# usb_ppm-v0_2.net
KiCad netlist of a schematic drawn in EAGLE
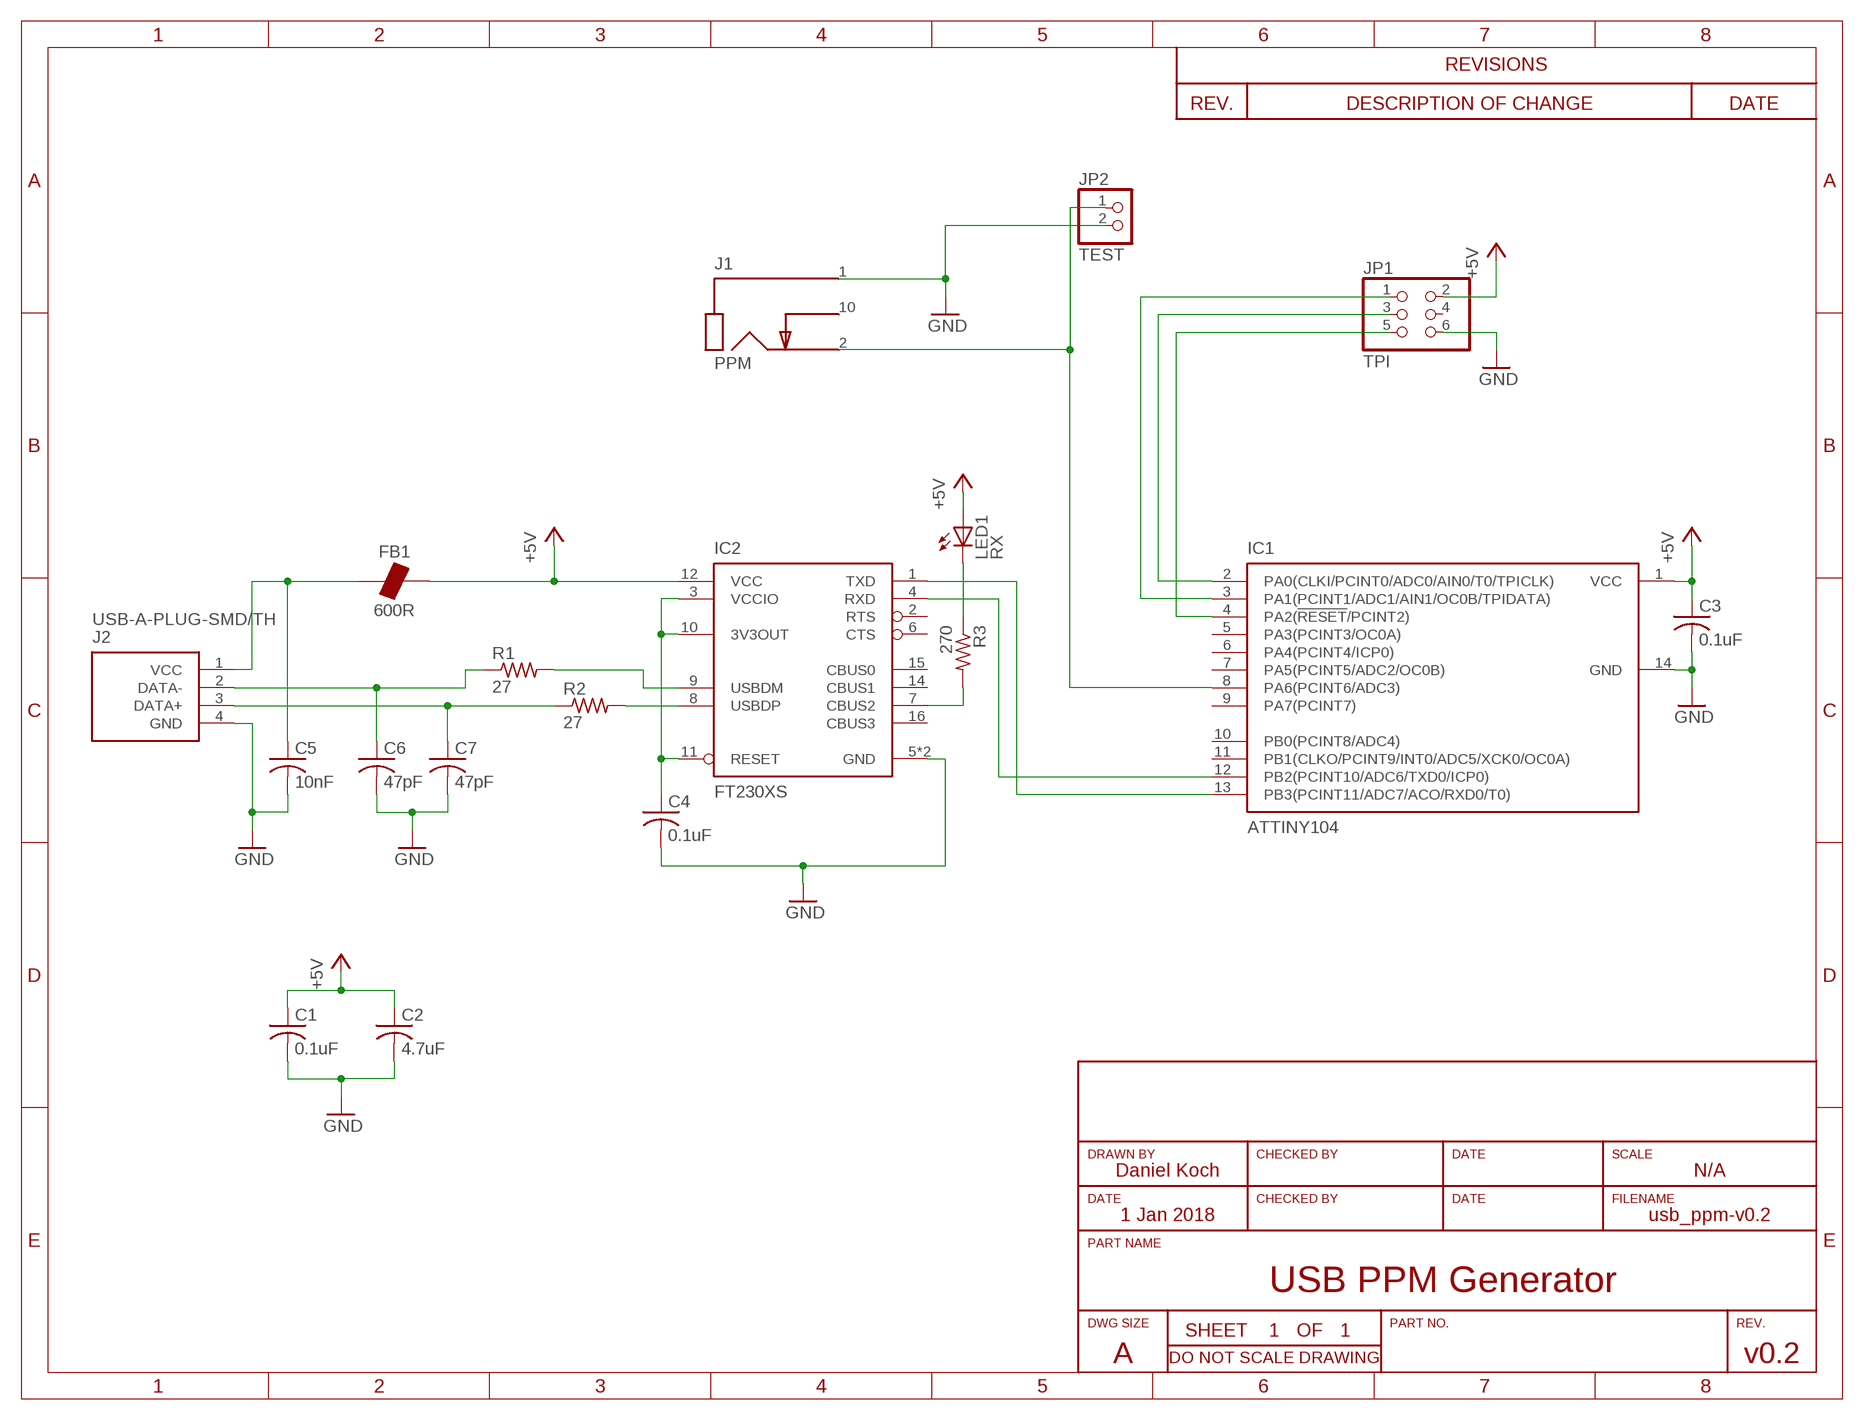
[diagram p0: schematic, sheet 1]

(export (version "E")
  (design (tool "Eeschema 10.0.6"))
  (components
    (comp (ref "C1")
      (value "0.1uF")
      (footprint "eagle-import:C0603")
      (libsource (lib "eagle-import") (part "C-USC0603"))
    )
    (comp (ref "C2")
      (value "4.7uF")
      (footprint "eagle-import:C0603")
      (libsource (lib "eagle-import") (part "C-USC0603"))
    )
    (comp (ref "C3")
      (value "0.1uF")
      (footprint "eagle-import:C0603")
      (libsource (lib "eagle-import") (part "C-USC0603"))
    )
    (comp (ref "C4")
      (value "0.1uF")
      (footprint "eagle-import:C0603")
      (libsource (lib "eagle-import") (part "C-USC0603"))
    )
    (comp (ref "C5")
      (value "10nF")
      (footprint "eagle-import:C0603")
      (libsource (lib "eagle-import") (part "C-USC0603"))
    )
    (comp (ref "C6")
      (value "47pF")
      (footprint "eagle-import:C0603")
      (libsource (lib "eagle-import") (part "C-USC0603"))
    )
    (comp (ref "C7")
      (value "47pF")
      (footprint "eagle-import:C0603")
      (libsource (lib "eagle-import") (part "C-USC0603"))
    )
    (comp (ref "FB1")
      (value "600R")
      (footprint "eagle-import:0603")
      (libsource (lib "eagle-import") (part "FB0603"))
    )
    (comp (ref "IC1")
      (value "ATTINY104")
      (footprint "eagle-import:SOIC-14")
      (libsource (lib "eagle-import") (part "ATTINY104"))
    )
    (comp (ref "IC2")
      (value "FT230XS")
      (footprint "eagle-import:SSOP-16")
      (libsource (lib "eagle-import") (part "FT230XS"))
    )
    (comp (ref "J1")
      (value "PPM")
      (footprint "eagle-import:MJ-3523-SMT")
      (libsource (lib "eagle-import") (part "MJ-3523-SMT"))
    )
    (comp (ref "J2")
      (value "USB-A-PLUG-SMD/TH")
      (footprint "eagle-import:USB-A-MALE-SMD_TH")
      (fields (field (name "MFG") "Molex, LLC"))
      (libsource (lib "eagle-import") (part "USB-A-PLUG-SMD/TH"))
    )
    (comp (ref "JP1")
      (value "TPI")
      (footprint "eagle-import:2X03")
      (libsource (lib "eagle-import") (part "PINHD-2X3"))
    )
    (comp (ref "JP2")
      (value "TEST")
      (footprint "eagle-import:1X02")
      (libsource (lib "eagle-import") (part "PINHD-1X2"))
    )
    (comp (ref "LED1")
      (value "RX")
      (footprint "eagle-import:CHIP-LED0603")
      (libsource (lib "eagle-import") (part "LEDCHIP-LED0603"))
    )
    (comp (ref "R1")
      (value "27")
      (footprint "eagle-import:R0603")
      (libsource (lib "eagle-import") (part "R-US_R0603"))
    )
    (comp (ref "R2")
      (value "27")
      (footprint "eagle-import:R0603")
      (libsource (lib "eagle-import") (part "R-US_R0603"))
    )
    (comp (ref "R3")
      (value "270")
      (footprint "eagle-import:R0603")
      (libsource (lib "eagle-import") (part "R-US_R0603"))
    )
  )
  (nets
    (net (code "1") (name "+5V") (class "Default")
      (node (ref "C1") (pin "1") (pinfunction "1_1") (pintype "passive"))
      (node (ref "C2") (pin "1") (pinfunction "1_1") (pintype "passive"))
      (node (ref "C3") (pin "1") (pinfunction "1_1") (pintype "passive"))
      (node (ref "FB1") (pin "2") (pinfunction "2_2") (pintype "passive"))
      (node (ref "IC1") (pin "1") (pinfunction "VCC_1") (pintype "power_in"))
      (node (ref "IC2") (pin "12") (pinfunction "VCC_12") (pintype "power_in"))
      (node (ref "JP1") (pin "2") (pinfunction "2_2") (pintype "passive"))
      (node (ref "LED1") (pin "A") (pinfunction "A_A") (pintype "passive"))
    )
    (net (code "2") (name "GND") (class "Default")
      (node (ref "C1") (pin "2") (pinfunction "2_2") (pintype "passive"))
      (node (ref "C2") (pin "2") (pinfunction "2_2") (pintype "passive"))
      (node (ref "C3") (pin "2") (pinfunction "2_2") (pintype "passive"))
      (node (ref "C4") (pin "2") (pinfunction "2_2") (pintype "passive"))
      (node (ref "C5") (pin "2") (pinfunction "2_2") (pintype "passive"))
      (node (ref "C6") (pin "2") (pinfunction "2_2") (pintype "passive"))
      (node (ref "C7") (pin "2") (pinfunction "2_2") (pintype "passive"))
      (node (ref "IC1") (pin "14") (pinfunction "GND_14") (pintype "power_in"))
      (node (ref "IC2") (pin "13") (pinfunction "GND_13") (pintype "power_in"))
      (node (ref "IC2") (pin "5") (pinfunction "GND_5") (pintype "power_in"))
      (node (ref "J1") (pin "1") (pinfunction "SLEEVE_1") (pintype "bidirectional"))
      (node (ref "J2") (pin "4") (pinfunction "GND_4") (pintype "power_in"))
      (node (ref "JP1") (pin "6") (pinfunction "6_6") (pintype "passive"))
      (node (ref "JP2") (pin "2") (pinfunction "2_2") (pintype "passive"))
    )
    (net (code "3") (name "Net-(IC1-PA0(CLKI{slash}PCINT0{slash}ADC0{slash}AIN0{slash}T0{slash}TPICLK))") (class "Default")
      (node (ref "IC1") (pin "2") (pinfunction "PA0(CLKI/PCINT0/ADC0/AIN0/T0/TPICLK)_2") (pintype "bidirectional"))
      (node (ref "JP1") (pin "3") (pinfunction "3_3") (pintype "passive"))
    )
    (net (code "4") (name "Net-(IC1-PA1(PCINT1{slash}ADC1{slash}AIN1{slash}OC0B{slash}TPIDATA))") (class "Default")
      (node (ref "IC1") (pin "3") (pinfunction "PA1(PCINT1/ADC1/AIN1/OC0B/TPIDATA)_3") (pintype "bidirectional"))
      (node (ref "JP1") (pin "1") (pinfunction "1_1") (pintype "passive"))
    )
    (net (code "5") (name "Net-(IC1-PA2(~{RESET}{slash}PCINT2))") (class "Default")
      (node (ref "IC1") (pin "4") (pinfunction "PA2(~{RESET}/PCINT2)_4") (pintype "bidirectional"))
      (node (ref "JP1") (pin "5") (pinfunction "5_5") (pintype "passive"))
    )
    (net (code "6") (name "Net-(IC1-PA6(PCINT6{slash}ADC3))") (class "Default")
      (node (ref "IC1") (pin "8") (pinfunction "PA6(PCINT6/ADC3)_8") (pintype "bidirectional"))
      (node (ref "J1") (pin "2") (pinfunction "TIP_2") (pintype "bidirectional"))
      (node (ref "JP2") (pin "1") (pinfunction "1_1") (pintype "passive"))
    )
    (net (code "7") (name "Net-(IC1-PB2(PCINT10{slash}ADC6{slash}TXD0{slash}ICP0))") (class "Default")
      (node (ref "IC1") (pin "12") (pinfunction "PB2(PCINT10/ADC6/TXD0/ICP0)_12") (pintype "bidirectional"))
      (node (ref "IC2") (pin "4") (pinfunction "RXD_4") (pintype "input"))
    )
    (net (code "8") (name "Net-(IC1-PB3(PCINT11{slash}ADC7{slash}ACO{slash}RXD0{slash}T0))") (class "Default")
      (node (ref "IC1") (pin "13") (pinfunction "PB3(PCINT11/ADC7/ACO/RXD0/T0)_13") (pintype "bidirectional"))
      (node (ref "IC2") (pin "1") (pinfunction "TXD_1") (pintype "output"))
    )
    (net (code "9") (name "Net-(IC2-3V3OUT)") (class "Default")
      (node (ref "C4") (pin "1") (pinfunction "1_1") (pintype "passive"))
      (node (ref "IC2") (pin "10") (pinfunction "3V3OUT_10") (pintype "power_in"))
      (node (ref "IC2") (pin "11") (pinfunction "RESET_11") (pintype "input"))
      (node (ref "IC2") (pin "3") (pinfunction "VCCIO_3") (pintype "power_in"))
    )
    (net (code "10") (name "Net-(IC2-CBUS2)") (class "Default")
      (node (ref "IC2") (pin "7") (pinfunction "CBUS2_7") (pintype "bidirectional"))
      (node (ref "R3") (pin "2") (pinfunction "2_2") (pintype "passive"))
    )
    (net (code "11") (name "Net-(IC2-USBDM)") (class "Default")
      (node (ref "IC2") (pin "9") (pinfunction "USBDM_9") (pintype "bidirectional"))
      (node (ref "R1") (pin "2") (pinfunction "2_2") (pintype "passive"))
    )
    (net (code "12") (name "Net-(IC2-USBDP)") (class "Default")
      (node (ref "IC2") (pin "8") (pinfunction "USBDP_8") (pintype "bidirectional"))
      (node (ref "R2") (pin "2") (pinfunction "2_2") (pintype "passive"))
    )
    (net (code "13") (name "Net-(J2-DATA+)") (class "Default")
      (node (ref "C7") (pin "1") (pinfunction "1_1") (pintype "passive"))
      (node (ref "J2") (pin "3") (pinfunction "DATA+_3") (pintype "bidirectional"))
      (node (ref "R2") (pin "1") (pinfunction "1_1") (pintype "passive"))
    )
    (net (code "14") (name "Net-(J2-DATA-)") (class "Default")
      (node (ref "C6") (pin "1") (pinfunction "1_1") (pintype "passive"))
      (node (ref "J2") (pin "2") (pinfunction "DATA-_2") (pintype "bidirectional"))
      (node (ref "R1") (pin "1") (pinfunction "1_1") (pintype "passive"))
    )
    (net (code "15") (name "Net-(J2-VCC)") (class "Default")
      (node (ref "C5") (pin "1") (pinfunction "1_1") (pintype "passive"))
      (node (ref "FB1") (pin "1") (pinfunction "1_1") (pintype "passive"))
      (node (ref "J2") (pin "1") (pinfunction "VCC_1") (pintype "power_in"))
    )
    (net (code "16") (name "Net-(LED1-PadC)") (class "Default")
      (node (ref "LED1") (pin "C") (pinfunction "C_C") (pintype "passive"))
      (node (ref "R3") (pin "1") (pinfunction "1_1") (pintype "passive"))
    )
    (net (code "17") (name "unconnected-(IC1-PA3(PCINT3{slash}OC0A)-Pad5)") (class "Default")
      (node (ref "IC1") (pin "5") (pinfunction "PA3(PCINT3/OC0A)_5") (pintype "bidirectional"))
    )
    (net (code "18") (name "unconnected-(IC1-PA4(PCINT4{slash}ICP0)-Pad6)") (class "Default")
      (node (ref "IC1") (pin "6") (pinfunction "PA4(PCINT4/ICP0)_6") (pintype "bidirectional"))
    )
    (net (code "19") (name "unconnected-(IC1-PA5(PCINT5{slash}ADC2{slash}OC0B)-Pad7)") (class "Default")
      (node (ref "IC1") (pin "7") (pinfunction "PA5(PCINT5/ADC2/OC0B)_7") (pintype "bidirectional"))
    )
    (net (code "20") (name "unconnected-(IC1-PA7(PCINT7)-Pad9)") (class "Default")
      (node (ref "IC1") (pin "9") (pinfunction "PA7(PCINT7)_9") (pintype "bidirectional"))
    )
    (net (code "21") (name "unconnected-(IC1-PB0(PCINT8{slash}ADC4)-Pad10)") (class "Default")
      (node (ref "IC1") (pin "10") (pinfunction "PB0(PCINT8/ADC4)_10") (pintype "bidirectional"))
    )
    (net (code "22") (name "unconnected-(IC1-PB1(CLKO{slash}PCINT9{slash}INT0{slash}ADC5{slash}XCK0{slash}OC0A)-Pad11)") (class "Default")
      (node (ref "IC1") (pin "11") (pinfunction "PB1(CLKO/PCINT9/INT0/ADC5/XCK0/OC0A)_11") (pintype "bidirectional"))
    )
    (net (code "23") (name "unconnected-(IC2-CBUS0-Pad15)") (class "Default")
      (node (ref "IC2") (pin "15") (pinfunction "CBUS0_15") (pintype "bidirectional"))
    )
    (net (code "24") (name "unconnected-(IC2-CBUS1-Pad14)") (class "Default")
      (node (ref "IC2") (pin "14") (pinfunction "CBUS1_14") (pintype "bidirectional"))
    )
    (net (code "25") (name "unconnected-(IC2-CBUS3-Pad16)") (class "Default")
      (node (ref "IC2") (pin "16") (pinfunction "CBUS3_16") (pintype "bidirectional"))
    )
    (net (code "26") (name "unconnected-(IC2-CTS-Pad6)") (class "Default")
      (node (ref "IC2") (pin "6") (pinfunction "CTS_6") (pintype "input"))
    )
    (net (code "27") (name "unconnected-(IC2-RTS-Pad2)") (class "Default")
      (node (ref "IC2") (pin "2") (pinfunction "RTS_2") (pintype "output"))
    )
    (net (code "28") (name "unconnected-(J1-SWITCH-Pad10)") (class "Default")
      (node (ref "J1") (pin "10") (pinfunction "SWITCH_10") (pintype "bidirectional"))
    )
    (net (code "29") (name "unconnected-(JP1-Pad4)") (class "Default")
      (node (ref "JP1") (pin "4") (pinfunction "4_4") (pintype "passive"))
    )
  )
)
